# Cansat2019_1516_Container_v01.net
KiCad netlist of a schematic drawn in EAGLE
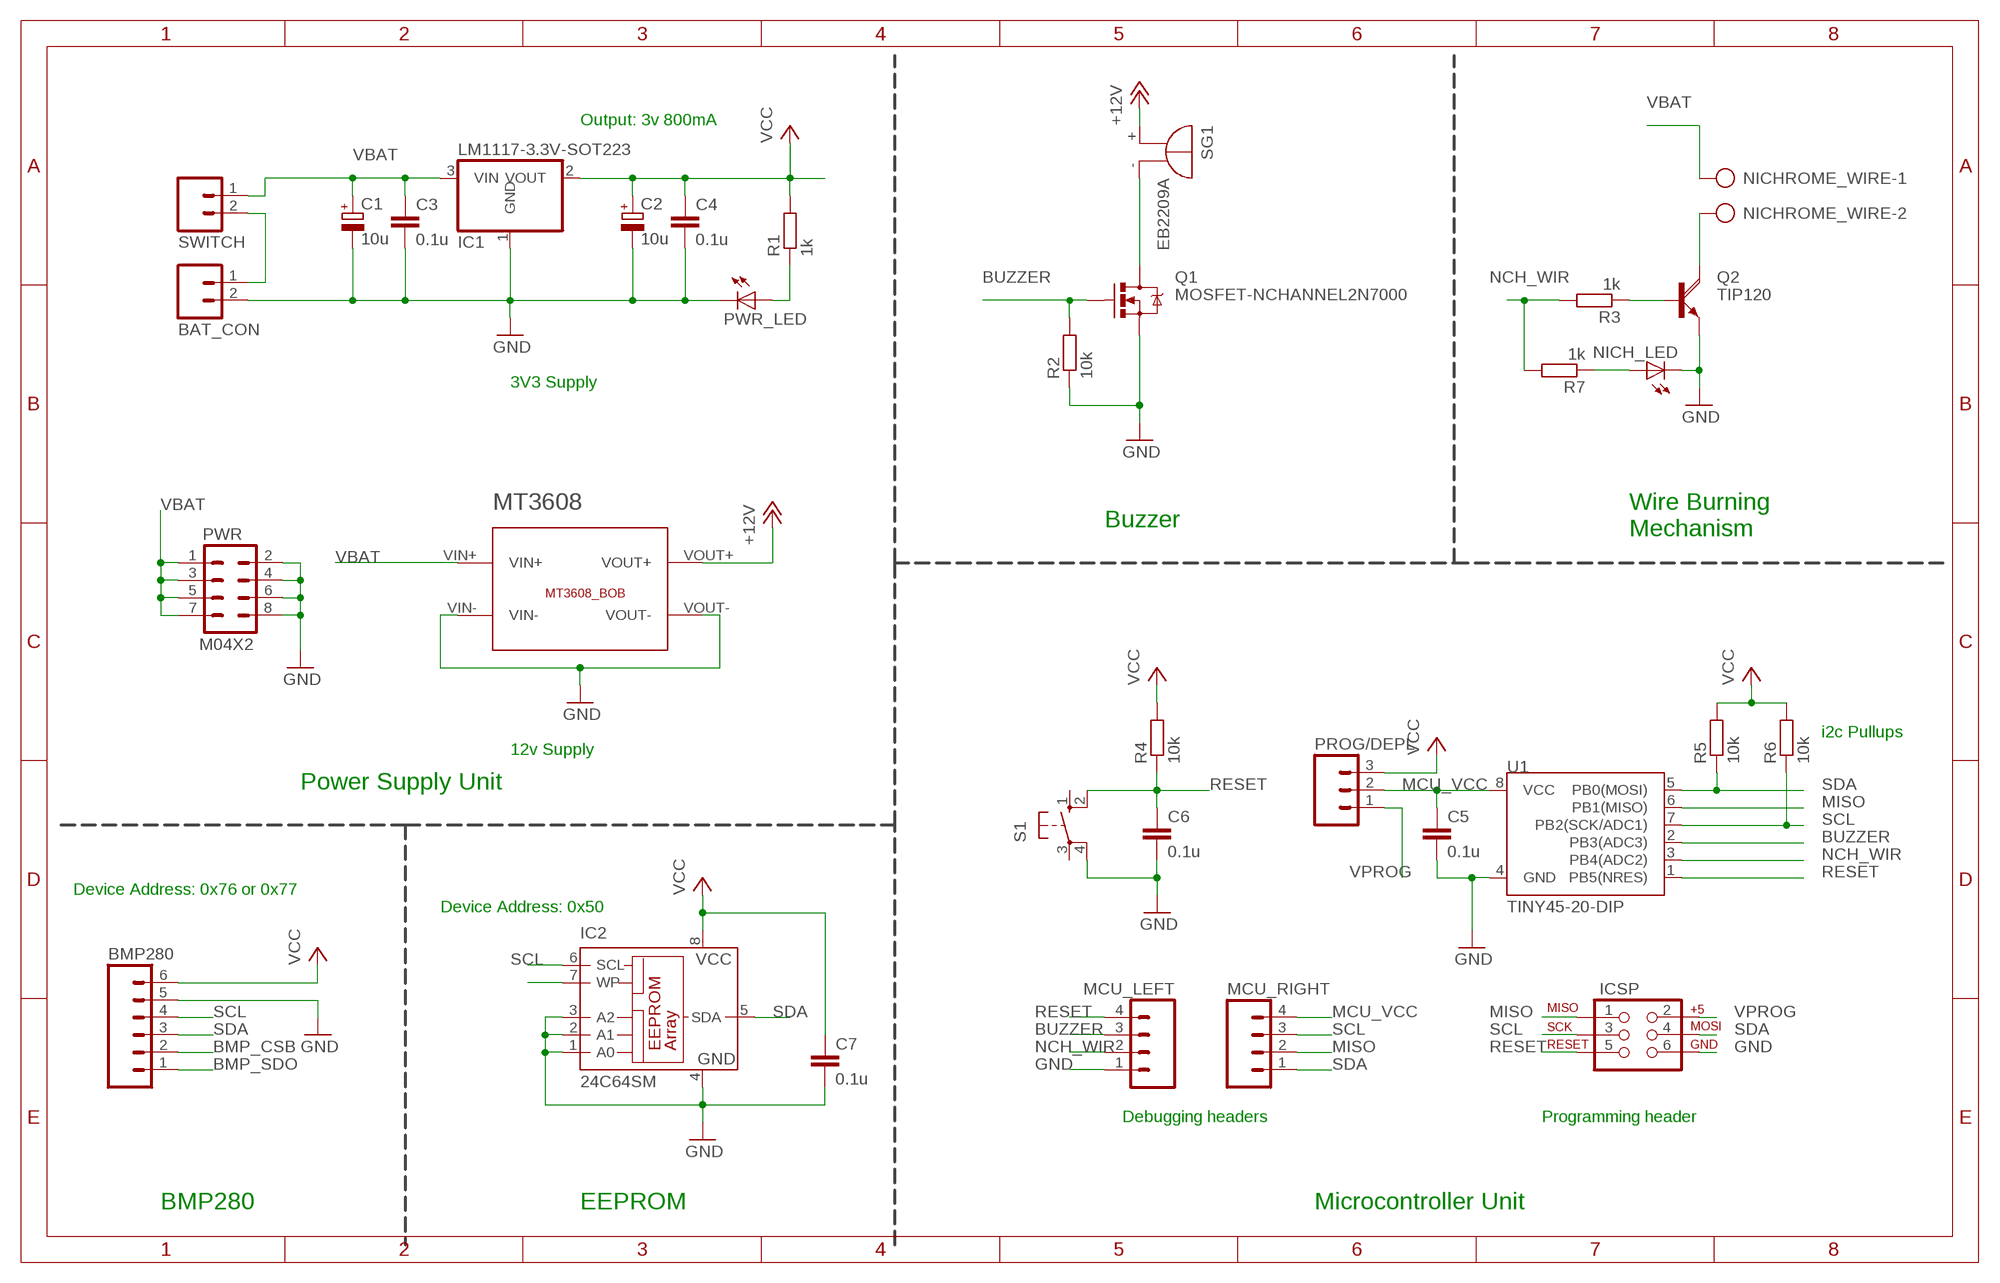
[diagram p0: schematic, sheet 1]

(export (version "E")
  (design (tool "Eeschema 10.0.6"))
  (components
    (comp (ref "BAT_CON")
      (value "M02")
      (footprint "eagle-import:02P")
      (libsource (lib "eagle-import") (part "M02"))
    )
    (comp (ref "BMP280")
      (value "M06")
      (footprint "eagle-import:06P")
      (libsource (lib "eagle-import") (part "M06"))
    )
    (comp (ref "C1")
      (value "10u")
      (footprint "eagle-import:E2,5-6")
      (libsource (lib "eagle-import") (part "CPOL-EUE2.5-6"))
    )
    (comp (ref "C2")
      (value "10u")
      (footprint "eagle-import:E2,5-6")
      (libsource (lib "eagle-import") (part "CPOL-EUE2.5-6"))
    )
    (comp (ref "C3")
      (value "0.1u")
      (footprint "eagle-import:C025-025X050")
      (libsource (lib "eagle-import") (part "C-EU025-025X050"))
    )
    (comp (ref "C4")
      (value "0.1u")
      (footprint "eagle-import:C025-025X050")
      (libsource (lib "eagle-import") (part "C-EU025-025X050"))
    )
    (comp (ref "C5")
      (value "0.1u")
      (footprint "eagle-import:C025-025X050")
      (libsource (lib "eagle-import") (part "C-EU025-025X050"))
    )
    (comp (ref "C6")
      (value "0.1u")
      (footprint "eagle-import:C025-025X050")
      (libsource (lib "eagle-import") (part "C-EU025-025X050"))
    )
    (comp (ref "C7")
      (value "0.1u")
      (footprint "eagle-import:C025-025X050")
      (libsource (lib "eagle-import") (part "C-EU025-025X050"))
    )
    (comp (ref "IC1")
      (value "LM1117-3.3V-SOT223")
      (footprint "eagle-import:SOT223")
      (libsource (lib "eagle-import") (part "LM1117-SOT223-3.3V"))
    )
    (comp (ref "IC2")
      (value "24C64SM")
      (footprint "eagle-import:SO-08M")
      (fields (field (name "MF") "RAMTRON INTERNATIONAL CORP") (field (name "MPN") "FM24C64-S"))
      (libsource (lib "eagle-import") (part "24SMC64"))
    )
    (comp (ref "ICSP")
      (value "AVR_SPI_PRG_6NS")
      (footprint "eagle-import:2X3-NS")
      (libsource (lib "eagle-import") (part "AVR_SPI_PRG_6NS"))
    )
    (comp (ref "MCU_LEFT")
      (value "M04")
      (footprint "eagle-import:04P")
      (libsource (lib "eagle-import") (part "M04"))
    )
    (comp (ref "MCU_RIGHT")
      (value "M04")
      (footprint "eagle-import:04P")
      (libsource (lib "eagle-import") (part "M04"))
    )
    (comp (ref "MT3608")
      (value "MT3608_BOB")
      (footprint "eagle-import:MT3608_BOB")
      (libsource (lib "eagle-import") (part "MT3608_BOB"))
    )
    (comp (ref "NICHROME_WIRE")
      (value "AK500/2-H")
      (footprint "eagle-import:AK500_2-H")
      (libsource (lib "eagle-import") (part "AK500/2-H"))
    )
    (comp (ref "NICH_LED")
      (value "LED3MM")
      (footprint "eagle-import:LED3MM")
      (libsource (lib "eagle-import") (part "LED3MM"))
    )
    (comp (ref "PROG/DEPL")
      (value "M03PTH")
      (footprint "eagle-import:1X03")
      (libsource (lib "eagle-import") (part "M03PTH"))
    )
    (comp (ref "PWR")
      (value "M04X2")
      (footprint "eagle-import:2X4")
      (libsource (lib "eagle-import") (part "M04X2"))
    )
    (comp (ref "PWR_LED")
      (value "LED3MM")
      (footprint "eagle-import:LED3MM")
      (libsource (lib "eagle-import") (part "LED3MM"))
    )
    (comp (ref "Q1")
      (value "MOSFET-NCHANNEL2N7000")
      (footprint "eagle-import:TO-92")
      (libsource (lib "eagle-import") (part "MOSFET-NCHANNEL2N7000"))
    )
    (comp (ref "Q2")
      (value "TIP120")
      (footprint "eagle-import:TO220AH")
      (libsource (lib "eagle-import") (part "TIP120"))
    )
    (comp (ref "R1")
      (value "1k")
      (footprint "eagle-import:0204_7")
      (libsource (lib "eagle-import") (part "R-EU_0204/7"))
    )
    (comp (ref "R2")
      (value "10k")
      (footprint "eagle-import:0204_7")
      (libsource (lib "eagle-import") (part "R-EU_0204/7"))
    )
    (comp (ref "R3")
      (value "1k")
      (footprint "eagle-import:0204_7")
      (libsource (lib "eagle-import") (part "R-EU_0204/7"))
    )
    (comp (ref "R4")
      (value "10k")
      (footprint "eagle-import:0204_7")
      (libsource (lib "eagle-import") (part "R-EU_0204/7"))
    )
    (comp (ref "R5")
      (value "10k")
      (footprint "eagle-import:0204_7")
      (libsource (lib "eagle-import") (part "R-EU_0204/7"))
    )
    (comp (ref "R6")
      (value "10k")
      (footprint "eagle-import:0204_7")
      (libsource (lib "eagle-import") (part "R-EU_0204/7"))
    )
    (comp (ref "R7")
      (value "1k")
      (footprint "eagle-import:0204_7")
      (libsource (lib "eagle-import") (part "R-EU_0204/7"))
    )
    (comp (ref "S1")
      (value "PUSH-BUTTON-6MM")
      (footprint "eagle-import:B3F-10XX")
      (libsource (lib "eagle-import") (part "PUSH-BUTTON-6MM"))
    )
    (comp (ref "SG1")
      (value "EB2209A")
      (footprint "eagle-import:EB2209A")
      (libsource (lib "eagle-import") (part "EB2209A"))
    )
    (comp (ref "SWITCH")
      (value "M02")
      (footprint "eagle-import:02P")
      (libsource (lib "eagle-import") (part "M02"))
    )
    (comp (ref "U1")
      (value "TINY45-20-DIP")
      (footprint "eagle-import:DIP08")
      (libsource (lib "eagle-import") (part "ATTINY45TINY45-20-DIP"))
    )
  )
  (nets
    (net (code "1") (name "+12V") (class "Default")
      (node (ref "MT3608") (pin "VOUT+") (pinfunction "VOUT+_VOUT+") (pintype "bidirectional"))
      (node (ref "SG1") (pin "+") (pinfunction "+_+") (pintype "passive"))
    )
    (net (code "2") (name "/BMP_CSB") (class "Default")
      (node (ref "BMP280") (pin "2") (pinfunction "2_2") (pintype "passive"))
    )
    (net (code "3") (name "/BMP_SDO") (class "Default")
      (node (ref "BMP280") (pin "1") (pinfunction "1_1") (pintype "passive"))
    )
    (net (code "4") (name "/BUZZER") (class "Default")
      (node (ref "MCU_LEFT") (pin "3") (pinfunction "3_3") (pintype "passive"))
      (node (ref "Q1") (pin "2") (pinfunction "G_2") (pintype "passive"))
      (node (ref "R2") (pin "2") (pinfunction "2_2") (pintype "passive"))
      (node (ref "U1") (pin "2") (pinfunction "PB3(ADC3)_2") (pintype "bidirectional"))
    )
    (net (code "5") (name "/MCU_VCC") (class "Default")
      (node (ref "C5") (pin "1") (pinfunction "1_1") (pintype "passive"))
      (node (ref "MCU_RIGHT") (pin "4") (pinfunction "4_4") (pintype "passive"))
      (node (ref "PROG/DEPL") (pin "2") (pinfunction "2_2") (pintype "passive"))
      (node (ref "U1") (pin "8") (pinfunction "VCC_8") (pintype "bidirectional"))
    )
    (net (code "6") (name "/MISO") (class "Default")
      (node (ref "ICSP") (pin "1") (pinfunction "1_1") (pintype "passive"))
      (node (ref "MCU_RIGHT") (pin "2") (pinfunction "2_2") (pintype "passive"))
      (node (ref "U1") (pin "6") (pinfunction "PB1(MISO)_6") (pintype "bidirectional"))
    )
    (net (code "7") (name "/NCH_WIR") (class "Default")
      (node (ref "MCU_LEFT") (pin "2") (pinfunction "2_2") (pintype "passive"))
      (node (ref "R3") (pin "2") (pinfunction "2_2") (pintype "passive"))
      (node (ref "R7") (pin "2") (pinfunction "2_2") (pintype "passive"))
      (node (ref "U1") (pin "3") (pinfunction "PB4(ADC2)_3") (pintype "bidirectional"))
    )
    (net (code "8") (name "/RESET") (class "Default")
      (node (ref "C6") (pin "1") (pinfunction "1_1") (pintype "passive"))
      (node (ref "ICSP") (pin "5") (pinfunction "5_5") (pintype "passive"))
      (node (ref "MCU_LEFT") (pin "4") (pinfunction "4_4") (pintype "passive"))
      (node (ref "R4") (pin "1") (pinfunction "1_1") (pintype "passive"))
      (node (ref "S1") (pin "2") (pinfunction "S1_2") (pintype "passive"))
      (node (ref "U1") (pin "1") (pinfunction "PB5(NRES)_1") (pintype "bidirectional"))
    )
    (net (code "9") (name "/SCL") (class "Default")
      (node (ref "BMP280") (pin "4") (pinfunction "4_4") (pintype "passive"))
      (node (ref "IC2") (pin "6") (pinfunction "SCL_6") (pintype "input"))
      (node (ref "ICSP") (pin "3") (pinfunction "3_3") (pintype "passive"))
      (node (ref "MCU_RIGHT") (pin "3") (pinfunction "3_3") (pintype "passive"))
      (node (ref "R6") (pin "1") (pinfunction "1_1") (pintype "passive"))
      (node (ref "U1") (pin "7") (pinfunction "PB2(SCK/ADC1)_7") (pintype "bidirectional"))
    )
    (net (code "10") (name "/SDA") (class "Default")
      (node (ref "BMP280") (pin "3") (pinfunction "3_3") (pintype "passive"))
      (node (ref "IC2") (pin "5") (pinfunction "SDA_5") (pintype "bidirectional"))
      (node (ref "ICSP") (pin "4") (pinfunction "4_4") (pintype "passive"))
      (node (ref "MCU_RIGHT") (pin "1") (pinfunction "1_1") (pintype "passive"))
      (node (ref "R5") (pin "1") (pinfunction "1_1") (pintype "passive"))
      (node (ref "U1") (pin "5") (pinfunction "PB0(MOSI)_5") (pintype "bidirectional"))
    )
    (net (code "11") (name "/VBAT") (class "Default")
      (node (ref "C1") (pin "+") (pinfunction "+_+") (pintype "passive"))
      (node (ref "C3") (pin "1") (pinfunction "1_1") (pintype "passive"))
      (node (ref "IC1") (pin "3") (pinfunction "VIN_3") (pintype "input"))
      (node (ref "MT3608") (pin "VIN+") (pinfunction "VIN+_VIN+") (pintype "bidirectional"))
      (node (ref "NICHROME_WIRE") (pin "1") (pinfunction "KL_1") (pintype "passive"))
      (node (ref "PWR") (pin "1") (pinfunction "1_1") (pintype "passive"))
      (node (ref "PWR") (pin "3") (pinfunction "3_3") (pintype "passive"))
      (node (ref "PWR") (pin "5") (pinfunction "5_5") (pintype "passive"))
      (node (ref "PWR") (pin "7") (pinfunction "7_7") (pintype "passive"))
      (node (ref "SWITCH") (pin "1") (pinfunction "1_1") (pintype "passive"))
    )
    (net (code "12") (name "/VPROG") (class "Default")
      (node (ref "ICSP") (pin "2") (pinfunction "2_2") (pintype "passive"))
      (node (ref "PROG/DEPL") (pin "1") (pinfunction "1_1") (pintype "passive"))
    )
    (net (code "13") (name "GND") (class "Default")
      (node (ref "BAT_CON") (pin "2") (pinfunction "2_2") (pintype "passive"))
      (node (ref "BMP280") (pin "5") (pinfunction "5_5") (pintype "passive"))
      (node (ref "C1") (pin "-") (pinfunction "-_-") (pintype "passive"))
      (node (ref "C2") (pin "-") (pinfunction "-_-") (pintype "passive"))
      (node (ref "C3") (pin "2") (pinfunction "2_2") (pintype "passive"))
      (node (ref "C4") (pin "2") (pinfunction "2_2") (pintype "passive"))
      (node (ref "C5") (pin "2") (pinfunction "2_2") (pintype "passive"))
      (node (ref "C6") (pin "2") (pinfunction "2_2") (pintype "passive"))
      (node (ref "C7") (pin "2") (pinfunction "2_2") (pintype "passive"))
      (node (ref "IC1") (pin "1") (pinfunction "GND_1") (pintype "power_in"))
      (node (ref "IC2") (pin "1") (pinfunction "A0_1") (pintype "input"))
      (node (ref "IC2") (pin "2") (pinfunction "A1_2") (pintype "input"))
      (node (ref "IC2") (pin "3") (pinfunction "A2_3") (pintype "input"))
      (node (ref "IC2") (pin "4") (pinfunction "GND_4") (pintype "power_in"))
      (node (ref "ICSP") (pin "6") (pinfunction "6_6") (pintype "passive"))
      (node (ref "MCU_LEFT") (pin "1") (pinfunction "1_1") (pintype "passive"))
      (node (ref "MT3608") (pin "VIN-") (pinfunction "VIN-_VIN-") (pintype "bidirectional"))
      (node (ref "MT3608") (pin "VOUT-") (pinfunction "VOUT-_VOUT-") (pintype "bidirectional"))
      (node (ref "NICH_LED") (pin "K") (pinfunction "C_K") (pintype "passive"))
      (node (ref "PWR") (pin "2") (pinfunction "2_2") (pintype "passive"))
      (node (ref "PWR") (pin "4") (pinfunction "4_4") (pintype "passive"))
      (node (ref "PWR") (pin "6") (pinfunction "6_6") (pintype "passive"))
      (node (ref "PWR") (pin "8") (pinfunction "8_8") (pintype "passive"))
      (node (ref "PWR_LED") (pin "K") (pinfunction "C_K") (pintype "passive"))
      (node (ref "Q1") (pin "1") (pinfunction "S_1") (pintype "passive"))
      (node (ref "Q2") (pin "E") (pinfunction "E_E") (pintype "passive"))
      (node (ref "R2") (pin "1") (pinfunction "1_1") (pintype "passive"))
      (node (ref "S1") (pin "4") (pinfunction "P1_4") (pintype "passive"))
      (node (ref "U1") (pin "4") (pinfunction "GND_4") (pintype "bidirectional"))
    )
    (net (code "14") (name "Net-(BAT_CON-Pad1)") (class "Default")
      (node (ref "BAT_CON") (pin "1") (pinfunction "1_1") (pintype "passive"))
      (node (ref "SWITCH") (pin "2") (pinfunction "2_2") (pintype "passive"))
    )
    (net (code "15") (name "Net-(NICHROME_WIREB-KL)") (class "Default")
      (node (ref "NICHROME_WIRE") (pin "2") (pinfunction "KL_2") (pintype "passive"))
      (node (ref "Q2") (pin "C") (pinfunction "C_C") (pintype "passive"))
    )
    (net (code "16") (name "Net-(NICH_LED-PadA)") (class "Default")
      (node (ref "NICH_LED") (pin "A") (pinfunction "A_A") (pintype "passive"))
      (node (ref "R7") (pin "1") (pinfunction "1_1") (pintype "passive"))
    )
    (net (code "17") (name "Net-(PWR_LED-PadA)") (class "Default")
      (node (ref "PWR_LED") (pin "A") (pinfunction "A_A") (pintype "passive"))
      (node (ref "R1") (pin "1") (pinfunction "1_1") (pintype "passive"))
    )
    (net (code "18") (name "Net-(Q1-D)") (class "Default")
      (node (ref "Q1") (pin "3") (pinfunction "D_3") (pintype "passive"))
      (node (ref "SG1") (pin "-") (pinfunction "-_-") (pintype "passive"))
    )
    (net (code "19") (name "Net-(Q2-PadB)") (class "Default")
      (node (ref "Q2") (pin "B") (pinfunction "B_B") (pintype "passive"))
      (node (ref "R3") (pin "1") (pinfunction "1_1") (pintype "passive"))
    )
    (net (code "20") (name "VCC") (class "Default")
      (node (ref "BMP280") (pin "6") (pinfunction "6_6") (pintype "passive"))
      (node (ref "C2") (pin "+") (pinfunction "+_+") (pintype "passive"))
      (node (ref "C4") (pin "1") (pinfunction "1_1") (pintype "passive"))
      (node (ref "C7") (pin "1") (pinfunction "1_1") (pintype "passive"))
      (node (ref "IC1") (pin "2") (pinfunction "VOUT_2") (pintype "output"))
      (node (ref "IC2") (pin "8") (pinfunction "VCC_8") (pintype "power_in"))
      (node (ref "PROG/DEPL") (pin "3") (pinfunction "3_3") (pintype "passive"))
      (node (ref "R1") (pin "2") (pinfunction "2_2") (pintype "passive"))
      (node (ref "R4") (pin "2") (pinfunction "2_2") (pintype "passive"))
      (node (ref "R5") (pin "2") (pinfunction "2_2") (pintype "passive"))
      (node (ref "R6") (pin "2") (pinfunction "2_2") (pintype "passive"))
    )
    (net (code "21") (name "unconnected-(IC2-WP-Pad7)") (class "Default")
      (node (ref "IC2") (pin "7") (pinfunction "WP_7") (pintype "input"))
    )
    (net (code "22") (name "unconnected-(S1-P-Pad3)") (class "Default")
      (node (ref "S1") (pin "3") (pinfunction "P_3") (pintype "passive"))
    )
    (net (code "23") (name "unconnected-(S1-S-Pad1)") (class "Default")
      (node (ref "S1") (pin "1") (pinfunction "S_1") (pintype "passive"))
    )
  )
)
